# cc3d_addons.net
KiCad netlist of a schematic drawn in Altium Designer
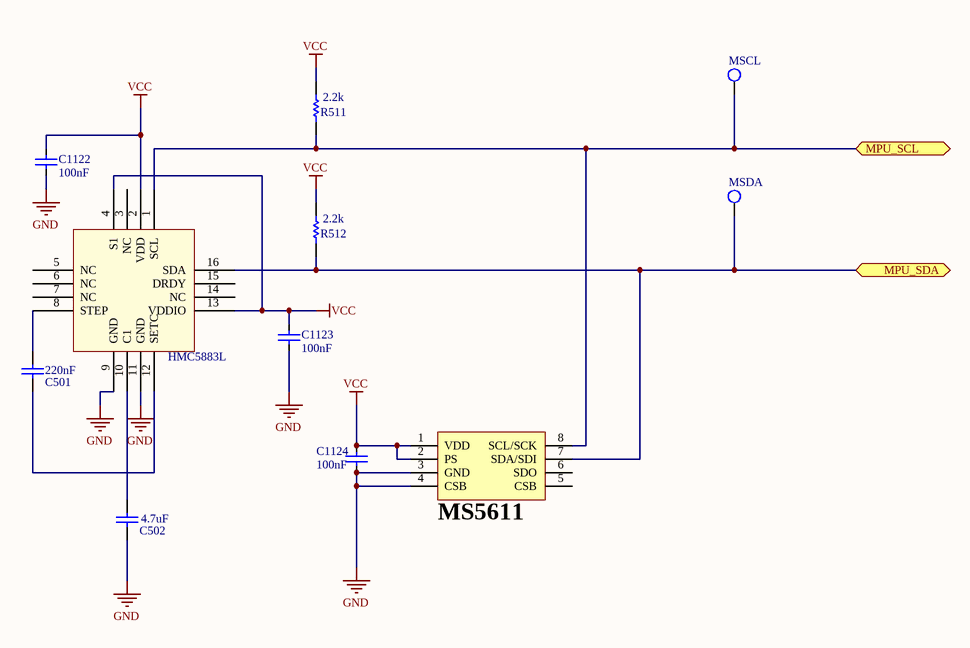
[diagram p0: cc3d_addons.SchDoc]

(export (version "E")
  (design (tool "Eeschema 10.0.6"))
  (components
    (comp (ref "C501")
      (value "220nF")
      (footprint "CAPC0603(1608)100_M")
      (description "CAP 220nF 6.3V ±10% 0603 (1608 Metric) Thickness 1mm SMD")
      (fields (field (name "TOLERANCE") "±10%") (field (name "Comment") "CAP 220nF 6.3V 0603(1608)"))
      (libsource (lib "Altium Content Vault") (part "CMP-1035-02636-1"))
    )
    (comp (ref "C502")
      (value "4.7uF")
      (footprint "CAPC0402(1005)60_L")
      (description "CAP 4.7uF 6.3V ±10% 0402 (1005 Metric) Thickness 0.6mm SMD")
      (fields (field (name "TOLERANCE") "±10%") (field (name "Comment") "CAP 4.7uF 6.3V 0402(1005)"))
      (libsource (lib "Altium Content Vault") (part "CMP-1034-02136-1"))
    )
    (comp (ref "C1122")
      (value "100nF")
      (footprint "CAP603L")
      (description "Capacitor SMD")
      (fields (field (name "Comment") "Cap603") (field (name "PUBLISHER") "The OpenPilot Project"))
      (libsource (lib "OpenPilot") (part "Cap603"))
    )
    (comp (ref "C1123")
      (value "100nF")
      (footprint "CAP603L")
      (description "Capacitor SMD")
      (fields (field (name "Comment") "Cap603") (field (name "PUBLISHER") "The OpenPilot Project"))
      (libsource (lib "OpenPilot") (part "Cap603"))
    )
    (comp (ref "C1124")
      (value "100nF")
      (footprint "CAP603L")
      (description "Capacitor SMD")
      (fields (field (name "Comment") "Cap603") (field (name "PUBLISHER") "The OpenPilot Project"))
      (libsource (lib "OpenPilot") (part "Cap603"))
    )
    (comp (ref "MG1")
      (value "HMC5883L")
      (footprint "HMC5883L")
      (libsource (lib "HMC5883L") (part "HMC5883L"))
    )
    (comp (ref "MS1")
      (value "MS5611")
      (footprint "MS5611")
      (description "Sensor")
      (libsource (lib "IMU") (part "MS5611"))
    )
    (comp (ref "MSCL")
      (value "TestPoint")
      (footprint "Tespoint_Keystone")
      (description "Testpoint")
      (libsource (lib "elevate_lib") (part "TestPoint"))
    )
    (comp (ref "MSDA")
      (value "Testpoint")
      (footprint "Tespoint_Keystone")
      (libsource (lib "elevate_lib") (part "TestPoint"))
    )
    (comp (ref "R511")
      (value "2.2k")
      (footprint "RESC0603(1608)_L")
      (description "2K2 0.1W 1% 0603 (1608 Metric)  SMD")
      (fields (field (name "TOLERANCE") "1 %") (field (name "POWER") "0.1 W"))
      (libsource (lib "Altium Content Vault") (part "CMP-1012-00546-1"))
    )
    (comp (ref "R512")
      (value "2.2k")
      (footprint "RESC0603(1608)_L")
      (description "2K2 0.1W 1% 0603 (1608 Metric)  SMD")
      (fields (field (name "TOLERANCE") "1 %") (field (name "POWER") "0.1 W"))
      (libsource (lib "Altium Content Vault") (part "CMP-1012-00546-1"))
    )
  )
  (nets
    (net (code "1") (name "/MPU_SCL") (class "Default")
      (node (ref "MG1") (pin "1") (pinfunction "SCL_1") (pintype "passive"))
      (node (ref "MS1") (pin "8") (pinfunction "SCL/SCK_8") (pintype "passive"))
      (node (ref "MSCL") (pin "1") (pinfunction "TP_1") (pintype "passive"))
      (node (ref "R511") (pin "1") (pinfunction "1_1") (pintype "passive"))
    )
    (net (code "2") (name "/MPU_SDA") (class "Default")
      (node (ref "MG1") (pin "16") (pinfunction "SDA_16") (pintype "passive"))
      (node (ref "MS1") (pin "7") (pinfunction "SDA/SDI_7") (pintype "passive"))
      (node (ref "MSDA") (pin "1") (pinfunction "TP_1") (pintype "passive"))
      (node (ref "R512") (pin "1") (pinfunction "1_1") (pintype "passive"))
    )
    (net (code "3") (name "GND") (class "Default")
      (node (ref "C1122") (pin "1") (pinfunction "1_1") (pintype "passive"))
      (node (ref "C1123") (pin "1") (pinfunction "1_1") (pintype "passive"))
      (node (ref "C1124") (pin "1") (pinfunction "1_1") (pintype "passive"))
      (node (ref "C502") (pin "1") (pinfunction "1_1") (pintype "passive"))
      (node (ref "MG1") (pin "11") (pinfunction "GND_11") (pintype "passive"))
      (node (ref "MG1") (pin "9") (pinfunction "GND_9") (pintype "passive"))
      (node (ref "MS1") (pin "3") (pinfunction "GND_3") (pintype "passive"))
      (node (ref "MS1") (pin "4") (pinfunction "CSB_4") (pintype "passive"))
    )
    (net (code "4") (name "Net-(MG1-C1)") (class "Default")
      (node (ref "C502") (pin "2") (pinfunction "2_2") (pintype "passive"))
      (node (ref "MG1") (pin "10") (pinfunction "C1_10") (pintype "passive"))
    )
    (net (code "5") (name "Net-(MG1-SETC)") (class "Default")
      (node (ref "C501") (pin "1") (pinfunction "1_1") (pintype "passive"))
      (node (ref "MG1") (pin "12") (pinfunction "SETC_12") (pintype "passive"))
    )
    (net (code "6") (name "Net-(MG1-STEP)") (class "Default")
      (node (ref "C501") (pin "2") (pinfunction "2_2") (pintype "passive"))
      (node (ref "MG1") (pin "8") (pinfunction "STEP_8") (pintype "passive"))
    )
    (net (code "7") (name "VCC") (class "Default")
      (node (ref "C1122") (pin "2") (pinfunction "2_2") (pintype "passive"))
      (node (ref "C1123") (pin "2") (pinfunction "2_2") (pintype "passive"))
      (node (ref "C1124") (pin "2") (pinfunction "2_2") (pintype "passive"))
      (node (ref "MG1") (pin "13") (pinfunction "VDDIO_13") (pintype "passive"))
      (node (ref "MG1") (pin "2") (pinfunction "VDD_2") (pintype "passive"))
      (node (ref "MG1") (pin "4") (pinfunction "S1_4") (pintype "passive"))
      (node (ref "MS1") (pin "1") (pinfunction "VDD_1") (pintype "passive"))
      (node (ref "MS1") (pin "2") (pinfunction "PS_2") (pintype "passive"))
      (node (ref "R511") (pin "2") (pinfunction "2_2") (pintype "passive"))
      (node (ref "R512") (pin "2") (pinfunction "2_2") (pintype "passive"))
    )
    (net (code "8") (name "unconnected-(MG1-DRDY-Pad15)") (class "Default")
      (node (ref "MG1") (pin "15") (pinfunction "DRDY_15") (pintype "passive"))
    )
    (net (code "9") (name "unconnected-(MG1-NC-Pad3)") (class "Default")
      (node (ref "MG1") (pin "3") (pinfunction "NC_3") (pintype "passive"))
    )
    (net (code "10") (name "unconnected-(MG1-NC-Pad5)") (class "Default")
      (node (ref "MG1") (pin "5") (pinfunction "NC_5") (pintype "passive"))
    )
    (net (code "11") (name "unconnected-(MG1-NC-Pad6)") (class "Default")
      (node (ref "MG1") (pin "6") (pinfunction "NC_6") (pintype "passive"))
    )
    (net (code "12") (name "unconnected-(MG1-NC-Pad7)") (class "Default")
      (node (ref "MG1") (pin "7") (pinfunction "NC_7") (pintype "passive"))
    )
    (net (code "13") (name "unconnected-(MG1-NC-Pad14)") (class "Default")
      (node (ref "MG1") (pin "14") (pinfunction "NC_14") (pintype "passive"))
    )
    (net (code "14") (name "unconnected-(MS1-CSB-Pad5)") (class "Default")
      (node (ref "MS1") (pin "5") (pinfunction "CSB_5") (pintype "passive"))
    )
    (net (code "15") (name "unconnected-(MS1-SDO-Pad6)") (class "Default")
      (node (ref "MS1") (pin "6") (pinfunction "SDO_6") (pintype "passive"))
    )
  )
)
